# 1_Main_copy.net
KiCad netlist of a schematic drawn in Altium Designer
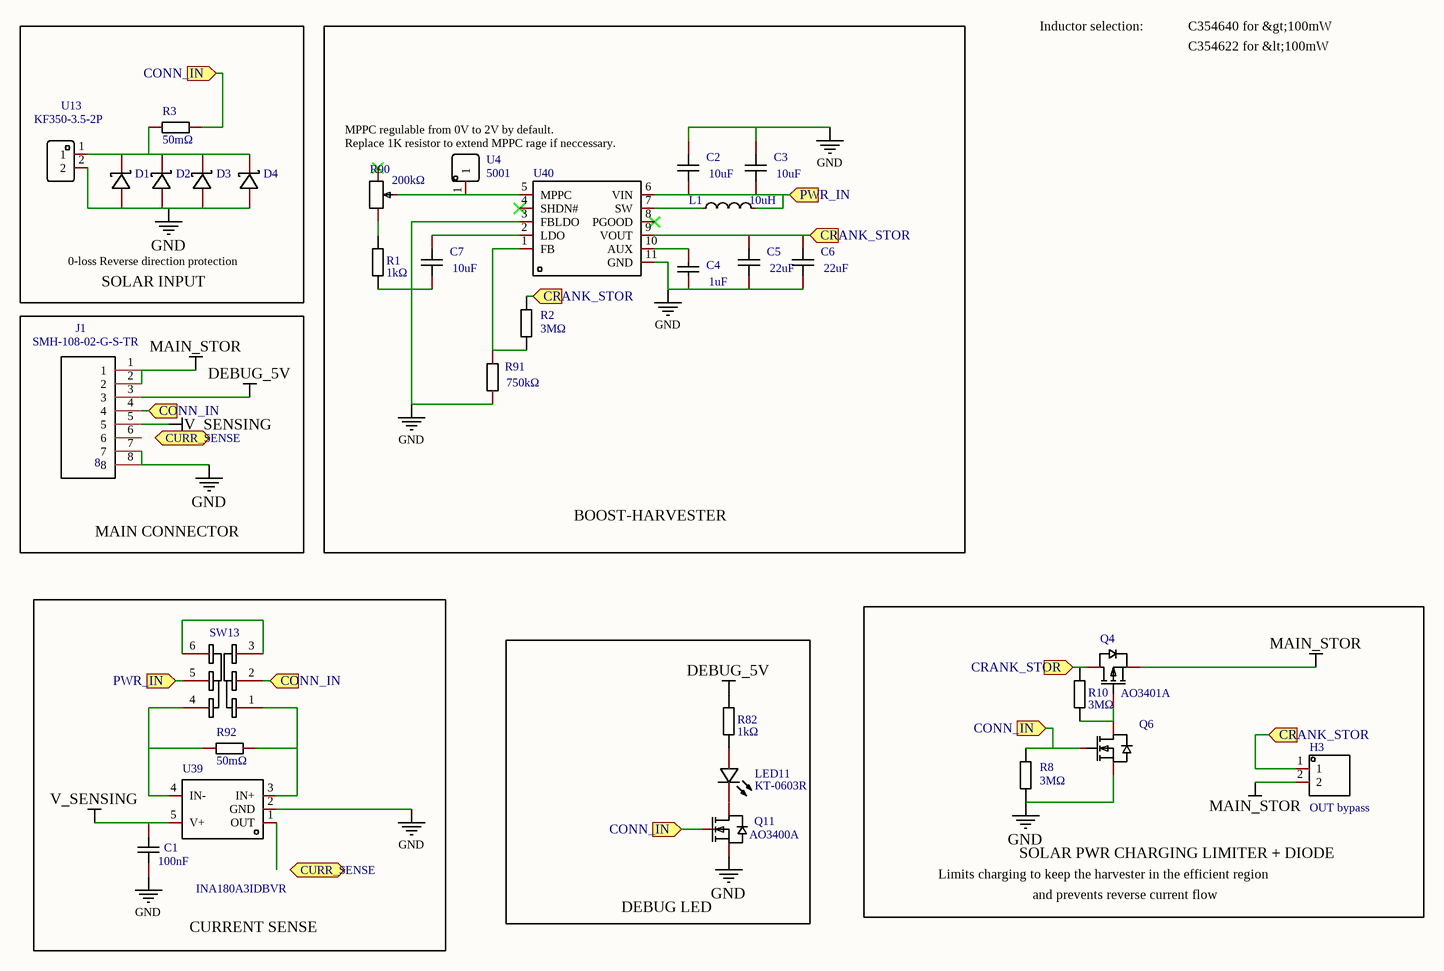
[diagram p0: 1_Main copy.schdoc]

(export (version "E")
  (design (tool "Eeschema 10.0.6"))
  (components
    (comp (ref "C1")
      (value "100nF")
      (fields
        (field (name "NAME") "100nF")
        (field (name "MANUFACTURER") "YAGEO")
        (field (name "MANUFACTURER PART") "CC0603KRX7R9BB104")
      )
      (libsource (lib "altium-import") (part "root_1_CC0603KRX7R9BB104_"))
    )
    (comp (ref "C2")
      (value "10uF")
      (fields
        (field (name "MANUFACTURER") "SAMSUNG(三星)")
        (field (name "MANUFACTURER PART") "CL10A106MA8NRNC")
        (field (name "TOLERANCE") "±20%")
      )
      (libsource (lib "altium-import") (part "root_1_CL10A106MA8NRNC_"))
    )
    (comp (ref "C3")
      (value "10uF")
      (fields
        (field (name "MANUFACTURER") "SAMSUNG(三星)")
        (field (name "MANUFACTURER PART") "CL10A106MA8NRNC")
        (field (name "TOLERANCE") "±20%")
      )
      (libsource (lib "altium-import") (part "root_1_CL10A106MA8NRNC_"))
    )
    (comp (ref "C4")
      (value "1uF")
      (fields
        (field (name "MANUFACTURER") "SAMSUNG(三星)")
        (field (name "MANUFACTURER PART") "CL10A105KB8NNNC")
        (field (name "TOLERANCE") "±10%")
      )
      (libsource (lib "altium-import") (part "root_1_CL10A105KB8NNNC_"))
    )
    (comp (ref "C5")
      (value "22uF")
      (fields
        (field (name "MANUFACTURER") "SAMSUNG(三星)")
        (field (name "MANUFACTURER PART") "CL21A226MAQNNNE")
        (field (name "TOLERANCE") "±20%")
      )
      (libsource (lib "altium-import") (part "root_1_CL21A226MAQNNNE_C45783_"))
    )
    (comp (ref "C6")
      (value "22uF")
      (fields
        (field (name "MANUFACTURER") "SAMSUNG(三星)")
        (field (name "MANUFACTURER PART") "CL21A226MAQNNNE")
        (field (name "TOLERANCE") "±20%")
      )
      (libsource (lib "altium-import") (part "root_1_CL21A226MAQNNNE_C45783_"))
    )
    (comp (ref "C7")
      (value "10uF")
      (fields
        (field (name "MANUFACTURER") "SAMSUNG(三星)")
        (field (name "MANUFACTURER PART") "CL10A106MA8NRNC")
        (field (name "TOLERANCE") "±20%")
      )
      (libsource (lib "altium-import") (part "root_1_CL10A106MA8NRNC_"))
    )
    (comp (ref "D1")
      (value "SS54")
      (description "Reverse Voltage (Vr):40V Average Rectified Current (Io):5A Forward Voltage (Vf@If):550mV@5A")
      (fields (field (name "MANUFACTURER") "MDD"))
      (libsource (lib "altium-import") (part "root_3_SS54_"))
    )
    (comp (ref "D2")
      (value "SS54")
      (description "Reverse Voltage (Vr):40V Average Rectified Current (Io):5A Forward Voltage (Vf@If):550mV@5A")
      (fields (field (name "MANUFACTURER") "MDD"))
      (libsource (lib "altium-import") (part "root_3_SS54_"))
    )
    (comp (ref "D3")
      (value "SS54")
      (description "Reverse Voltage (Vr):40V Average Rectified Current (Io):5A Forward Voltage (Vf@If):550mV@5A")
      (fields (field (name "MANUFACTURER") "MDD"))
      (libsource (lib "altium-import") (part "root_3_SS54_"))
    )
    (comp (ref "D4")
      (value "SS54")
      (description "Reverse Voltage (Vr):40V Average Rectified Current (Io):5A Forward Voltage (Vf@If):550mV@5A")
      (fields (field (name "MANUFACTURER") "MDD"))
      (libsource (lib "altium-import") (part "root_3_SS54_"))
    )
    (comp (ref "H3")
      (value "OUT bypass")
      (fields (field (name "NAME") "OUT bypass"))
      (libsource (lib "altium-import") (part "root_0_HDR-M_2.54_1x2P_"))
    )
    (comp (ref "J1")
      (value "SMH-108-02-G-S-TR")
      (fields (field (name "NAME") "SMH-108-02-G-S-TR") (field (name "NAME_1") "8"))
      (libsource (lib "altium-import") (part "root_0_SMH-108-02-G-S-TR_"))
    )
    (comp (ref "L1")
      (value "10uH")
      (fields (field (name "MANUFACTURER") "CENKER(岑科)") (field (name "MANUFACTURER PART") "CKCS6028-10uH/M"))
      (libsource (lib "altium-import") (part "root_0_CKCS6028-10uH/M_"))
    )
    (comp (ref "LED11")
      (value "KT-0603R")
      (fields (field (name "NAME") "KT-0603R") (field (name "MANUFACTURER") "KENTO"))
      (libsource (lib "altium-import") (part "root_1_KT-0603R_"))
    )
    (comp (ref "Q4")
      (value "AO3401A")
      (fields (field (name "NAME") "AO3401A") (field (name "MANUFACTURER") "AOS"))
      (libsource (lib "altium-import") (part "root_1_mirrored_AO3401A_"))
    )
    (comp (ref "Q6")
      (value "SI2302")
      (fields (field (name "MANUFACTURER") "YONGYUTAI(永裕泰)"))
      (libsource (lib "altium-import") (part "root_0_SI2302_"))
    )
    (comp (ref "Q11")
      (value "AO3400A")
      (fields (field (name "NAME") "AO3400A") (field (name "MANUFACTURER") "HUASHUO(华朔)"))
      (libsource (lib "altium-import") (part "root_0_AO3400A_"))
    )
    (comp (ref "R1")
      (value "1kΩ")
      (fields
        (field (name "NAME") "1kΩ")
        (field (name "MANUFACTURER") "UniOhm")
        (field (name "MANUFACTURER PART") "0603WAF1001T5E")
      )
      (libsource (lib "altium-import") (part "root_1_0603WAF1001T5E_"))
    )
    (comp (ref "R2")
      (value "3MΩ")
      (fields
        (field (name "NAME") "3MΩ")
        (field (name "MANUFACTURER") "UniOhm")
        (field (name "MANUFACTURER PART") "0603WAF3004T5E")
      )
      (libsource (lib "altium-import") (part "root_3_0603WAF3004T5E_"))
    )
    (comp (ref "R3")
      (value "50mΩ")
      (fields
        (field (name "MANUFACTURER") "UNI-ROYAL(厚声)")
        (field (name "MANUFACTURER PART") "1206W3F500MT5E")
        (field (name "TOLERANCE") "±1%")
      )
      (libsource (lib "altium-import") (part "root_0_1206W3F500MT5E_C127691_"))
    )
    (comp (ref "R8")
      (value "3MΩ")
      (fields
        (field (name "NAME") "3MΩ")
        (field (name "MANUFACTURER") "UniOhm")
        (field (name "MANUFACTURER PART") "0603WAF3004T5E")
      )
      (libsource (lib "altium-import") (part "root_3_0603WAF3004T5E_"))
    )
    (comp (ref "R10")
      (value "3MΩ")
      (fields
        (field (name "NAME") "3MΩ")
        (field (name "MANUFACTURER") "UniOhm")
        (field (name "MANUFACTURER PART") "0603WAF3004T5E")
      )
      (libsource (lib "altium-import") (part "root_1_0603WAF3004T5E_"))
    )
    (comp (ref "R82")
      (value "1kΩ")
      (fields
        (field (name "NAME") "1kΩ")
        (field (name "MANUFACTURER") "UniOhm")
        (field (name "MANUFACTURER PART") "0603WAF1001T5E")
      )
      (libsource (lib "altium-import") (part "root_1_0603WAF1001T5E_"))
    )
    (comp (ref "R90")
      (value "200kΩ")
      (description "Resistance: Tolerance:±25% Tolerance:±25%")
      (fields (field (name "MANUFACTURER") "HDK(北陆电气)") (field (name "MANUFACTURER PART") "VG039NCHXTB204"))
      (libsource (lib "altium-import") (part "root_0_mirrored_VG039NCHXTB204_"))
    )
    (comp (ref "R91")
      (value "750kΩ")
      (fields
        (field (name "MANUFACTURER") "UNI-ROYAL(厚声)")
        (field (name "MANUFACTURER PART") "0603WAF7503T5E")
        (field (name "TOLERANCE") "±1%")
      )
      (libsource (lib "altium-import") (part "root_1_0603WAF7503T5E_"))
    )
    (comp (ref "R92")
      (value "50mΩ")
      (fields
        (field (name "MANUFACTURER") "UNI-ROYAL(厚声)")
        (field (name "MANUFACTURER PART") "1206W3F500MT5E")
        (field (name "TOLERANCE") "±1%")
      )
      (libsource (lib "altium-import") (part "root_0_1206W3F500MT5E_C127691_"))
    )
    (comp (ref "SW13")
      (value "K3-2235D-F1")
      (fields (field (name "MANUFACTURER") "韩国韩荣"))
      (libsource (lib "altium-import") (part "root_1_mirrored_K3-2235D-F1_"))
    )
    (comp (ref "U4")
      (value "5001")
      (fields (field (name "NAME") "5001") (field (name "MANUFACTURER") "Keystone"))
      (libsource (lib "altium-import") (part "root_1_5001_"))
    )
    (comp (ref "U13")
      (value "KF350-3.5-2P")
      (fields (field (name "NAME") "KF350-3.5-2P") (field (name "MANUFACTURER") "Cixi Kefa Elec"))
      (libsource (lib "altium-import") (part "root_2_KF350-3.5-2P_"))
    )
    (comp (ref "U39")
      (value "INA180A3IDBVR")
      (fields (field (name "LCSC PART NAME") "INA180A3IDBVR") (field (name "MANUFACTURER") "TI(德州仪器)"))
      (libsource (lib "altium-import") (part "root_2_INA180A3IDBVR_"))
    )
    (comp (ref "U40")
      (value "LTC3105EDD#PBF")
      (fields (field (name "MANUFACTURER") "ADI(亚德诺)/LINEAR(凌特)"))
      (libsource (lib "altium-import") (part "root_2_mirrored_LTC3105EDD#PBF_"))
    )
  )
  (nets
    (net (code "1") (name "/CONN_IN") (class "Default")
      (node (ref "J1") (pin "4") (pinfunction "4_4") (pintype "passive"))
      (node (ref "Q11") (pin "1") (pinfunction "G_1") (pintype "passive"))
      (node (ref "Q6") (pin "1") (pinfunction "G_1") (pintype "passive"))
      (node (ref "R3") (pin "2") (pinfunction "2_2") (pintype "passive"))
      (node (ref "R8") (pin "1") (pinfunction "1_1") (pintype "passive"))
      (node (ref "SW13") (pin "2") (pinfunction "2_2") (pintype "passive"))
    )
    (net (code "2") (name "/CRANK_STOR") (class "Default")
      (node (ref "C5") (pin "2") (pinfunction "2_2") (pintype "passive"))
      (node (ref "C6") (pin "2") (pinfunction "2_2") (pintype "passive"))
      (node (ref "H3") (pin "1") (pinfunction "1_1") (pintype "passive"))
      (node (ref "Q4") (pin "3") (pinfunction "D_3") (pintype "passive"))
      (node (ref "R10") (pin "2") (pinfunction "2_2") (pintype "passive"))
      (node (ref "R2") (pin "1") (pinfunction "1_1") (pintype "passive"))
      (node (ref "U40") (pin "9") (pinfunction "VOUT_9") (pintype "passive"))
    )
    (net (code "4") (name "/PWR_IN") (class "Default")
      (node (ref "C2") (pin "1") (pinfunction "1_1") (pintype "passive"))
      (node (ref "C3") (pin "1") (pinfunction "1_1") (pintype "passive"))
      (node (ref "L1") (pin "2") (pinfunction "2_2") (pintype "passive"))
      (node (ref "SW13") (pin "5") (pinfunction "5_5") (pintype "passive"))
      (node (ref "U40") (pin "6") (pinfunction "VIN_6") (pintype "passive"))
    )
    (net (code "5") (name "DEBUG_5V") (class "Default")
      (node (ref "J1") (pin "3") (pinfunction "3_3") (pintype "passive"))
      (node (ref "R82") (pin "2") (pinfunction "2_2") (pintype "passive"))
    )
    (net (code "6") (name "GND") (class "Default")
      (node (ref "C1") (pin "1") (pinfunction "1_1") (pintype "passive"))
      (node (ref "C2") (pin "2") (pinfunction "2_2") (pintype "passive"))
      (node (ref "C3") (pin "2") (pinfunction "2_2") (pintype "passive"))
      (node (ref "C4") (pin "1") (pinfunction "1_1") (pintype "passive"))
      (node (ref "C5") (pin "1") (pinfunction "1_1") (pintype "passive"))
      (node (ref "C6") (pin "1") (pinfunction "1_1") (pintype "passive"))
      (node (ref "C7") (pin "1") (pinfunction "1_1") (pintype "passive"))
      (node (ref "D1") (pin "1") (pinfunction "A_1") (pintype "passive"))
      (node (ref "D2") (pin "1") (pinfunction "A_1") (pintype "passive"))
      (node (ref "D3") (pin "1") (pinfunction "A_1") (pintype "passive"))
      (node (ref "D4") (pin "1") (pinfunction "A_1") (pintype "passive"))
      (node (ref "J1") (pin "7") (pinfunction "7_7") (pintype "passive"))
      (node (ref "J1") (pin "8") (pinfunction "8_8") (pintype "passive"))
      (node (ref "Q11") (pin "2") (pinfunction "S_2") (pintype "passive"))
      (node (ref "Q6") (pin "2") (pinfunction "S_2") (pintype "passive"))
      (node (ref "R1") (pin "1") (pinfunction "1_1") (pintype "passive"))
      (node (ref "R8") (pin "2") (pinfunction "2_2") (pintype "passive"))
      (node (ref "R91") (pin "1") (pinfunction "1_1") (pintype "passive"))
      (node (ref "U13") (pin "2") (pinfunction "2_2") (pintype "passive"))
      (node (ref "U39") (pin "2") (pinfunction "GND_2") (pintype "passive"))
      (node (ref "U40") (pin "11") (pinfunction "GND_11") (pintype "passive"))
      (node (ref "U40") (pin "3") (pinfunction "FBLDO_3") (pintype "passive"))
    )
    (net (code "7") (name "MAIN_STOR") (class "Default")
      (node (ref "H3") (pin "2") (pinfunction "2_2") (pintype "passive"))
      (node (ref "J1") (pin "1") (pinfunction "1_1") (pintype "passive"))
      (node (ref "J1") (pin "2") (pinfunction "2_2") (pintype "passive"))
      (node (ref "Q4") (pin "2") (pinfunction "S_2") (pintype "passive"))
    )
    (net (code "8") (name "Net-(D1-K)") (class "Default")
      (node (ref "D1") (pin "2") (pinfunction "K_2") (pintype "passive"))
      (node (ref "D2") (pin "2") (pinfunction "K_2") (pintype "passive"))
      (node (ref "D3") (pin "2") (pinfunction "K_2") (pintype "passive"))
      (node (ref "D4") (pin "2") (pinfunction "K_2") (pintype "passive"))
      (node (ref "R3") (pin "1") (pinfunction "1_1") (pintype "passive"))
      (node (ref "U13") (pin "1") (pinfunction "1_1") (pintype "passive"))
    )
    (net (code "9") (name "Net-(LED11-A)") (class "Default")
      (node (ref "LED11") (pin "1") (pinfunction "A_1") (pintype "passive"))
      (node (ref "R82") (pin "1") (pinfunction "1_1") (pintype "passive"))
    )
    (net (code "10") (name "Net-(LED11-K)") (class "Default")
      (node (ref "LED11") (pin "2") (pinfunction "K_2") (pintype "passive"))
      (node (ref "Q11") (pin "3") (pinfunction "D_3") (pintype "passive"))
    )
    (net (code "11") (name "Net-(Q4-G)") (class "Default")
      (node (ref "Q4") (pin "1") (pinfunction "G_1") (pintype "passive"))
      (node (ref "Q6") (pin "3") (pinfunction "D_3") (pintype "passive"))
      (node (ref "R10") (pin "1") (pinfunction "1_1") (pintype "passive"))
    )
    (net (code "12") (name "Net-(R1-Pad2)") (class "Default")
      (node (ref "R1") (pin "2") (pinfunction "2_2") (pintype "passive"))
      (node (ref "R90") (pin "1") (pinfunction "1_1") (pintype "passive"))
    )
    (net (code "13") (name "Net-(SW13-Pad3)") (class "Default")
      (node (ref "SW13") (pin "3") (pinfunction "3_3") (pintype "passive"))
      (node (ref "SW13") (pin "6") (pinfunction "6_6") (pintype "passive"))
    )
    (net (code "14") (name "Net-(U39-IN+)") (class "Default")
      (node (ref "R92") (pin "2") (pinfunction "2_2") (pintype "passive"))
      (node (ref "SW13") (pin "1") (pinfunction "1_1") (pintype "passive"))
      (node (ref "U39") (pin "3") (pinfunction "IN+_3") (pintype "passive"))
    )
    (net (code "15") (name "Net-(U39-IN-)") (class "Default")
      (node (ref "R92") (pin "1") (pinfunction "1_1") (pintype "passive"))
      (node (ref "SW13") (pin "4") (pinfunction "4_4") (pintype "passive"))
      (node (ref "U39") (pin "4") (pinfunction "IN-_4") (pintype "passive"))
    )
    (net (code "16") (name "Net-(U40-AUX)") (class "Default")
      (node (ref "C4") (pin "2") (pinfunction "2_2") (pintype "passive"))
      (node (ref "U40") (pin "10") (pinfunction "AUX_10") (pintype "passive"))
    )
    (net (code "17") (name "Net-(U40-FB)") (class "Default")
      (node (ref "R2") (pin "2") (pinfunction "2_2") (pintype "passive"))
      (node (ref "R91") (pin "2") (pinfunction "2_2") (pintype "passive"))
      (node (ref "U40") (pin "1") (pinfunction "FB_1") (pintype "passive"))
    )
    (net (code "18") (name "Net-(U40-LDO)") (class "Default")
      (node (ref "C7") (pin "2") (pinfunction "2_2") (pintype "passive"))
      (node (ref "U40") (pin "2") (pinfunction "LDO_2") (pintype "passive"))
    )
    (net (code "19") (name "Net-(U40-MPPC)") (class "Default")
      (node (ref "R90") (pin "2") (pinfunction "2_2") (pintype "passive"))
      (node (ref "U4") (pin "1") (pinfunction "1_1") (pintype "passive"))
      (node (ref "U40") (pin "5") (pinfunction "MPPC_5") (pintype "passive"))
    )
    (net (code "20") (name "Net-(U40-SW)") (class "Default")
      (node (ref "L1") (pin "1") (pinfunction "1_1") (pintype "passive"))
      (node (ref "U40") (pin "7") (pinfunction "SW_7") (pintype "passive"))
    )
    (net (code "21") (name "V_SENSING") (class "Default")
      (node (ref "C1") (pin "2") (pinfunction "2_2") (pintype "passive"))
      (node (ref "J1") (pin "5") (pinfunction "5_5") (pintype "passive"))
      (node (ref "U39") (pin "5") (pinfunction "V+_5") (pintype "passive"))
    )
    (net (code "22") (name "unconnected-(J1-Pad6)") (class "Default")
      (node (ref "J1") (pin "6") (pinfunction "6_6") (pintype "passive"))
    )
    (net (code "23") (name "unconnected-(R90-Pad3)") (class "Default")
      (node (ref "R90") (pin "3") (pinfunction "3_3") (pintype "passive+no_connect"))
    )
    (net (code "24") (name "unconnected-(U39-OUT-Pad1)") (class "Default")
      (node (ref "U39") (pin "1") (pinfunction "OUT_1") (pintype "passive"))
    )
    (net (code "25") (name "unconnected-(U40-PGOOD-Pad8)") (class "Default")
      (node (ref "U40") (pin "8") (pinfunction "PGOOD_8") (pintype "passive+no_connect"))
    )
    (net (code "26") (name "unconnected-(U40-SHDN#-Pad4)") (class "Default")
      (node (ref "U40") (pin "4") (pinfunction "SHDN#_4") (pintype "passive+no_connect"))
    )
  )
)
